# CAN_IFC.net
KiCad netlist of a schematic drawn in Altium Designer
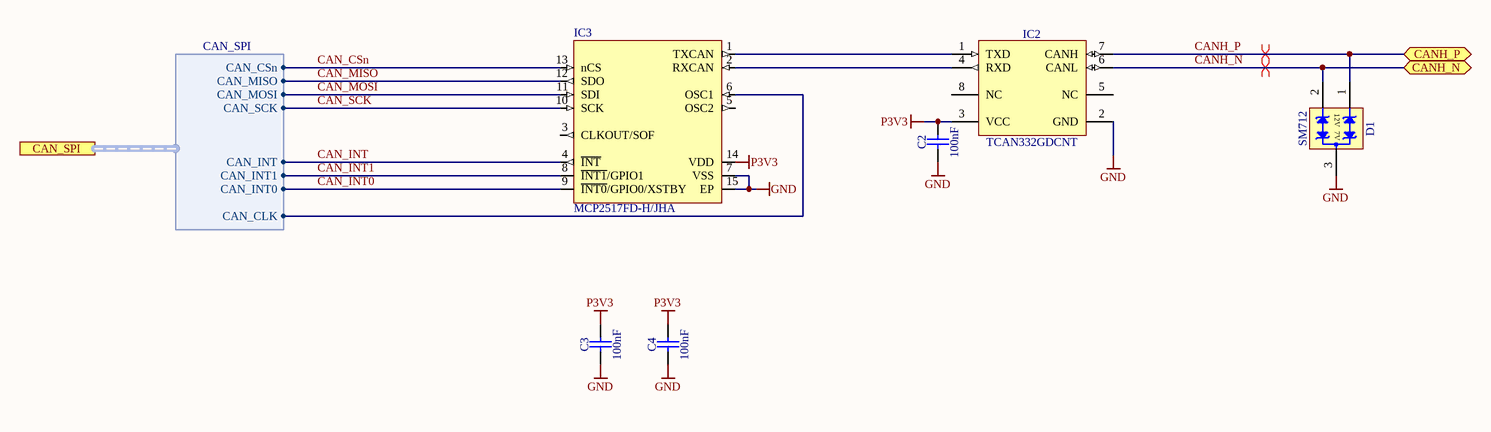
[diagram p0: CAN_IFC.SchDoc]

(export (version "E")
  (design (tool "Eeschema 10.0.6"))
  (components
    (comp (ref "C2")
      (value "100nF")
      (footprint "CAPC1005X55N")
      (description "Non-polarised capacitor")
      (fields
        (field (name "PART NUMBER") "CC0402_100NF_16V_10%_X5R")
        (field (name "VOLTAGE") "16V")
        (field (name "AUTHOR") "CERN DEM JLC")
      )
      (libsource (lib "Capacitors") (part "Capacitor - non polarized"))
    )
    (comp (ref "C3")
      (value "100nF")
      (footprint "CAPC1005X55N")
      (description "Non-polarised capacitor")
      (fields
        (field (name "PART NUMBER") "CC0402_100NF_16V_10%_X5R")
        (field (name "VOLTAGE") "16V")
        (field (name "AUTHOR") "CERN DEM JLC")
      )
      (libsource (lib "Capacitors") (part "Capacitor - non polarized"))
    )
    (comp (ref "C4")
      (value "100nF")
      (footprint "CAPC1005X55N")
      (description "Non-polarised capacitor")
      (fields
        (field (name "PART NUMBER") "CC0402_100NF_16V_10%_X5R")
        (field (name "VOLTAGE") "16V")
        (field (name "AUTHOR") "CERN DEM JLC")
      )
      (libsource (lib "Capacitors") (part "Capacitor - non polarized"))
    )
    (comp (ref "D1")
      (value "SM712")
      (footprint "SOT95P237X112-3N")
      (description "Asymmetrical TVS Diode for Extended Common-Mode RS-485")
      (fields
        (field (name "VOLTAGE") "12V/-7V")
        (field (name "POWER") "400W")
        (field (name "AUTHOR") "CERN DEM JLC")
      )
      (libsource (lib "ICs And Semiconductors") (part "SM712"))
    )
    (comp (ref "IC2")
      (value "TCAN332GDCNT")
      (footprint "SOT65P280X145-8N")
      (description "3.3V CAN Transceivers with CAN FD (Flexible Data Rate)")
      (fields (field (name "MANUFACTURER") "TEXAS INSTRUMENTS") (field (name "AUTHOR") "CERN DEM JLC"))
      (libsource (lib "ICs And Semiconductors") (part "TCAN332"))
    )
    (comp (ref "IC3")
      (value "MCP2517FD-H/JHA")
      (footprint "SON65P300X90_HS-15N")
      (description "External CAN FD Controller with SPI Interface")
      (fields (field (name "MANUFACTURER") "Microchip"))
      (libsource (lib "LIBRARY_SCH") (part "IFC_MCP2517"))
    )
  )
  (nets
    (net (code "2") (name "/CANH_N") (class "Default")
      (node (ref "D1") (pin "2") (pinfunction "I/O2_2") (pintype "passive"))
      (node (ref "IC2") (pin "6") (pinfunction "CANL_6") (pintype "bidirectional"))
    )
    (net (code "3") (name "/CANH_P") (class "Default")
      (node (ref "D1") (pin "1") (pinfunction "I/O1_1") (pintype "passive"))
      (node (ref "IC2") (pin "7") (pinfunction "CANH_7") (pintype "bidirectional"))
    )
    (net (code "4") (name "/CAN_CLK") (class "Default")
      (node (ref "IC3") (pin "6") (pinfunction "OSC1_6") (pintype "input"))
    )
    (net (code "5") (name "/CAN_CSn") (class "Default")
      (node (ref "IC3") (pin "13") (pinfunction "nCS_13") (pintype "input"))
    )
    (net (code "6") (name "/CAN_INT") (class "Default")
      (node (ref "IC3") (pin "4") (pinfunction "~{INT}_4") (pintype "output"))
    )
    (net (code "7") (name "/CAN_INT0") (class "Default")
      (node (ref "IC3") (pin "9") (pinfunction "~{INT0}/GPIO0/XSTBY_9") (pintype "bidirectional"))
    )
    (net (code "8") (name "/CAN_INT1") (class "Default")
      (node (ref "IC3") (pin "8") (pinfunction "~{INT1}/GPIO1_8") (pintype "bidirectional"))
    )
    (net (code "9") (name "/CAN_MISO") (class "Default")
      (node (ref "IC3") (pin "12") (pinfunction "SDO_12") (pintype "output"))
    )
    (net (code "10") (name "/CAN_MOSI") (class "Default")
      (node (ref "IC3") (pin "11") (pinfunction "SDI_11") (pintype "input"))
    )
    (net (code "11") (name "/CAN_SCK") (class "Default")
      (node (ref "IC3") (pin "10") (pinfunction "SCK_10") (pintype "input"))
    )
    (net (code "13") (name "GND") (class "Default")
      (node (ref "C2") (pin "1") (pinfunction "1_1") (pintype "passive"))
      (node (ref "C3") (pin "1") (pinfunction "1_1") (pintype "passive"))
      (node (ref "C4") (pin "1") (pinfunction "1_1") (pintype "passive"))
      (node (ref "D1") (pin "3") (pinfunction "GND_3") (pintype "passive"))
      (node (ref "IC2") (pin "2") (pinfunction "GND_2") (pintype "power_in"))
      (node (ref "IC3") (pin "15") (pinfunction "EP_15") (pintype "power_in"))
      (node (ref "IC3") (pin "7") (pinfunction "VSS_7") (pintype "power_in"))
    )
    (net (code "14") (name "Net-(IC2-RXD)") (class "Default")
      (node (ref "IC2") (pin "4") (pinfunction "RXD_4") (pintype "output"))
      (node (ref "IC3") (pin "2") (pinfunction "RXCAN_2") (pintype "input"))
    )
    (net (code "15") (name "Net-(IC2-TXD)") (class "Default")
      (node (ref "IC2") (pin "1") (pinfunction "TXD_1") (pintype "input"))
      (node (ref "IC3") (pin "1") (pinfunction "TXCAN_1") (pintype "output"))
    )
    (net (code "16") (name "P3V3") (class "Default")
      (node (ref "C2") (pin "2") (pinfunction "2_2") (pintype "passive"))
      (node (ref "C3") (pin "2") (pinfunction "2_2") (pintype "passive"))
      (node (ref "C4") (pin "2") (pinfunction "2_2") (pintype "passive"))
      (node (ref "IC2") (pin "3") (pinfunction "VCC_3") (pintype "power_in"))
      (node (ref "IC3") (pin "14") (pinfunction "VDD_14") (pintype "power_in"))
    )
    (net (code "17") (name "unconnected-(IC2-NC-Pad5)") (class "Default")
      (node (ref "IC2") (pin "5") (pinfunction "NC_5") (pintype "passive"))
    )
    (net (code "18") (name "unconnected-(IC2-NC-Pad8)") (class "Default")
      (node (ref "IC2") (pin "8") (pinfunction "NC_8") (pintype "passive"))
    )
    (net (code "19") (name "unconnected-(IC3-CLKOUT{slash}SOF-Pad3)") (class "Default")
      (node (ref "IC3") (pin "3") (pinfunction "CLKOUT/SOF_3") (pintype "output"))
    )
    (net (code "20") (name "unconnected-(IC3-OSC2-Pad5)") (class "Default")
      (node (ref "IC3") (pin "5") (pinfunction "OSC2_5") (pintype "output"))
    )
  )
)
